# CMOY_Pro_1_0.net
KiCad netlist of a schematic drawn in Altium Designer
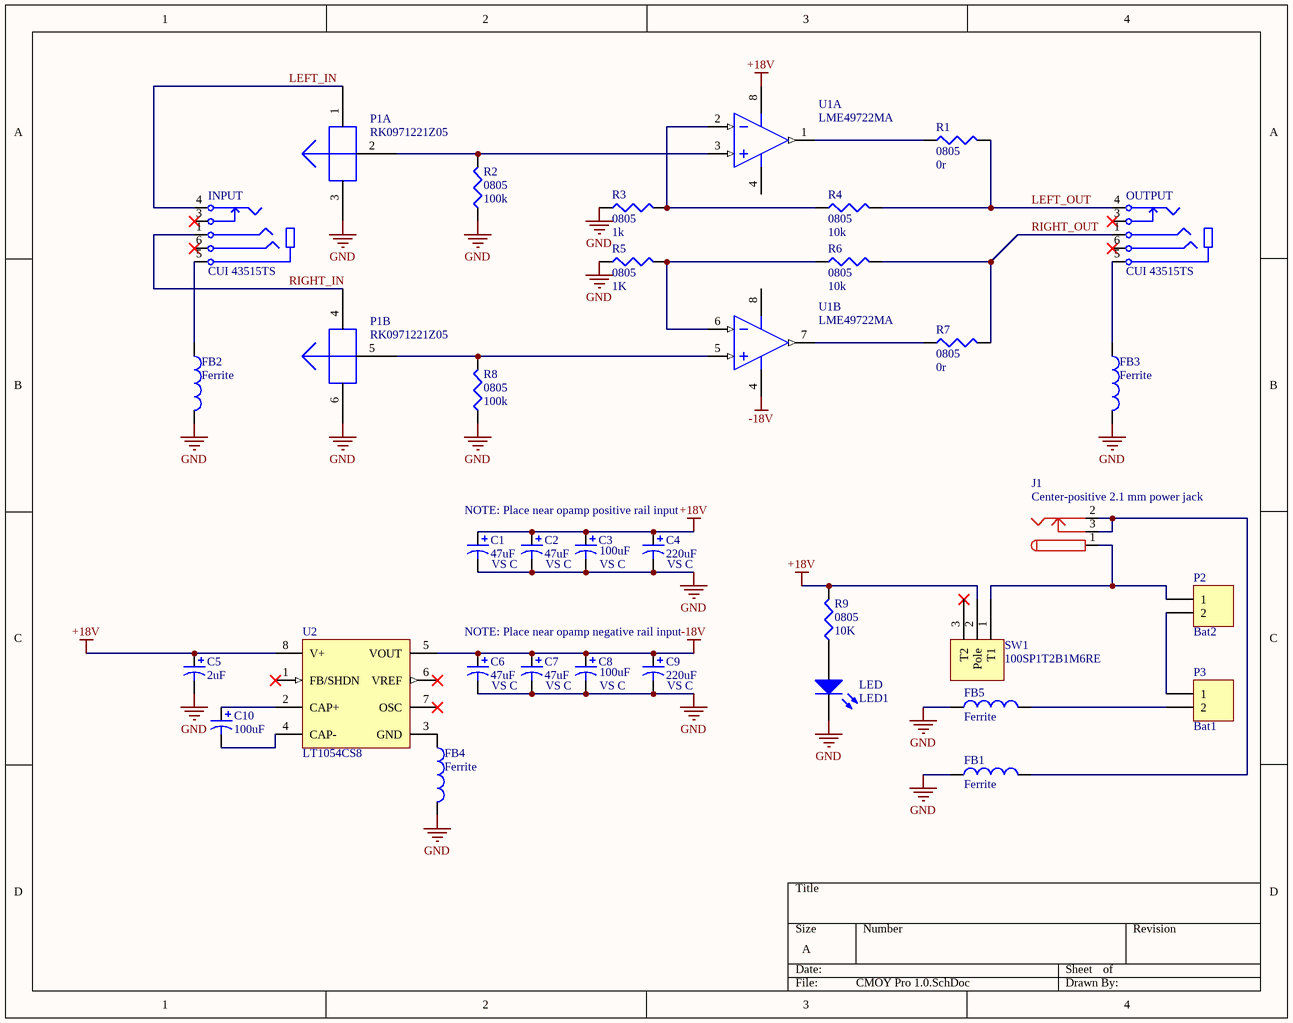
[diagram p0: CMOY Pro 1.0.SchDoc]

(export (version "E")
  (design (tool "Eeschema 10.0.6"))
  (components
    (comp (ref "C1")
      (value "VS C")
      (footprint "CAPPR2.5-6.3x5")
      (description "Polarized Capacitor (Radial)")
      (fields (field (name "ALTIUM_VALUE") "47uF") (field (name "PUBLISHER") "Altium Limited"))
      (libsource (lib "Miscellaneous Devices") (part "Cap Pol1"))
    )
    (comp (ref "C2")
      (value "VS C")
      (footprint "CAPPR2.5-6.3x5")
      (description "Polarized Capacitor (Radial)")
      (fields (field (name "ALTIUM_VALUE") "47uF") (field (name "PUBLISHER") "Altium Limited"))
      (libsource (lib "Miscellaneous Devices") (part "Cap Pol1"))
    )
    (comp (ref "C3")
      (value "VS C")
      (footprint "CAPPR2.5-6.3x5")
      (description "Polarized Capacitor (Radial)")
      (fields (field (name "ALTIUM_VALUE") "100uF") (field (name "PUBLISHER") "Altium Limited"))
      (libsource (lib "Miscellaneous Devices") (part "Cap Pol1"))
    )
    (comp (ref "C4")
      (value "VS C")
      (footprint "CAPPR2.5-6.3x5")
      (description "Polarized Capacitor (Radial)")
      (fields (field (name "ALTIUM_VALUE") "220uF") (field (name "PUBLISHER") "Altium Limited"))
      (libsource (lib "Miscellaneous Devices") (part "Cap Pol1"))
    )
    (comp (ref "C5")
      (value "2uF")
      (footprint "Panasonic VS C")
      (description "Polarized Capacitor (Radial)")
      (fields (field (name "Comment") "Cap Pol1") (field (name "PUBLISHER") "Altium Limited"))
      (libsource (lib "Miscellaneous Devices") (part "Cap Pol1"))
    )
    (comp (ref "C6")
      (value "VS C")
      (footprint "CAPPR2.5-6.3x5")
      (description "Polarized Capacitor (Radial)")
      (fields (field (name "ALTIUM_VALUE") "47uF") (field (name "PUBLISHER") "Altium Limited"))
      (libsource (lib "Miscellaneous Devices") (part "Cap Pol1"))
    )
    (comp (ref "C7")
      (value "VS C")
      (footprint "CAPPR2.5-6.3x5")
      (description "Polarized Capacitor (Radial)")
      (fields (field (name "ALTIUM_VALUE") "47uF") (field (name "PUBLISHER") "Altium Limited"))
      (libsource (lib "Miscellaneous Devices") (part "Cap Pol1"))
    )
    (comp (ref "C8")
      (value "VS C")
      (footprint "CAPPR2.5-6.3x5")
      (description "Polarized Capacitor (Radial)")
      (fields (field (name "ALTIUM_VALUE") "100uF") (field (name "PUBLISHER") "Altium Limited"))
      (libsource (lib "Miscellaneous Devices") (part "Cap Pol1"))
    )
    (comp (ref "C9")
      (value "VS C")
      (footprint "CAPPR2.5-6.3x5")
      (description "Polarized Capacitor (Radial)")
      (fields (field (name "ALTIUM_VALUE") "220uF") (field (name "PUBLISHER") "Altium Limited"))
      (libsource (lib "Miscellaneous Devices") (part "Cap Pol1"))
    )
    (comp (ref "C10")
      (value "100uF")
      (footprint "Panasonic VS C")
      (description "Polarized Capacitor (Radial)")
      (fields (field (name "Comment") "Cap Pol1") (field (name "PUBLISHER") "Altium Limited"))
      (libsource (lib "Miscellaneous Devices") (part "Cap Pol1"))
    )
    (comp (ref "FB1")
      (value "Ferrite")
      (footprint "SM 0805 - gap trimmed")
      (description "Inductor")
      (fields (field (name "PUBLISHER") "Altium Limited"))
      (libsource (lib "Miscellaneous Devices") (part "Inductor"))
    )
    (comp (ref "FB2")
      (value "Ferrite")
      (footprint "SM 0805 - gap trimmed")
      (description "Inductor")
      (fields (field (name "PUBLISHER") "Altium Limited"))
      (libsource (lib "Miscellaneous Devices") (part "Inductor"))
    )
    (comp (ref "FB3")
      (value "Ferrite")
      (footprint "SM 0805 - gap trimmed")
      (description "Inductor")
      (fields (field (name "PUBLISHER") "Altium Limited"))
      (libsource (lib "Miscellaneous Devices") (part "Inductor"))
    )
    (comp (ref "FB4")
      (value "Ferrite")
      (footprint "SM 0805 - gap trimmed")
      (description "Inductor")
      (fields (field (name "PUBLISHER") "Altium Limited"))
      (libsource (lib "Miscellaneous Devices") (part "Inductor"))
    )
    (comp (ref "FB5")
      (value "Ferrite")
      (footprint "SM 0805 - gap trimmed")
      (description "Inductor")
      (fields (field (name "PUBLISHER") "Altium Limited"))
      (libsource (lib "Miscellaneous Devices") (part "Inductor"))
    )
    (comp (ref "INPUT")
      (value "CUI 43515TS")
      (footprint "CUI SJ-43515TS")
      (libsource (lib "Adams Altium Library") (part "CUI 43515TS"))
    )
    (comp (ref "J1")
      (value "Center-positive 2.1 mm power jack")
      (footprint "PJ-102AH")
      (description "Power jack")
      (fields (field (name "PUBLISHER") "Altium Limited"))
      (libsource (lib "Adams Altium Library") (part "PWR2.5"))
    )
    (comp (ref "LED")
      (value "LED1")
      (footprint "SM 0805 polarized")
      (description "Typical RED GaAs LED")
      (fields (field (name "PUBLISHER") "Altium Limited"))
      (libsource (lib "Miscellaneous Devices") (part "LED1"))
    )
    (comp (ref "OUTPUT")
      (value "CUI 43515TS")
      (footprint "CUI SJ-43515TS")
      (libsource (lib "Adams Altium Library") (part "CUI 43515TS"))
    )
    (comp (ref "P1")
      (value "RK0971221Z05")
      (footprint "RK0971221Z05")
      (description "PCB Mount Dual Ganged 10K Pot")
      (libsource (lib "CMOY Pro Lib") (part "RK0971221Z05"))
    )
    (comp (ref "P2")
      (value "Bat2")
      (footprint "HDR1X2")
      (description "Header, 2-Pin")
      (fields (field (name "PUBLISHER") "Altium Limited"))
      (libsource (lib "Miscellaneous Connectors") (part "Header 2"))
    )
    (comp (ref "P3")
      (value "Bat1")
      (footprint "HDR1X2")
      (description "Header, 2-Pin")
      (fields (field (name "PUBLISHER") "Altium Limited"))
      (libsource (lib "Miscellaneous Connectors") (part "Header 2"))
    )
    (comp (ref "R1")
      (value "0805")
      (footprint "SM 0805 - gap trimmed")
      (description "Resistor")
      (fields (field (name "ALTIUM_VALUE") "0r") (field (name "PUBLISHER") "Altium Limited"))
      (libsource (lib "Miscellaneous Devices") (part "Res3"))
    )
    (comp (ref "R2")
      (value "0805")
      (footprint "SM 0805 - gap trimmed")
      (description "Resistor")
      (fields (field (name "ALTIUM_VALUE") "100k") (field (name "PUBLISHER") "Altium Limited"))
      (libsource (lib "Miscellaneous Devices") (part "Res3"))
    )
    (comp (ref "R3")
      (value "0805")
      (footprint "SM 0805 - gap trimmed")
      (description "Resistor")
      (fields (field (name "ALTIUM_VALUE") "1k") (field (name "PUBLISHER") "Altium Limited"))
      (libsource (lib "Miscellaneous Devices") (part "Res3"))
    )
    (comp (ref "R4")
      (value "0805")
      (footprint "SM 0805 - gap trimmed")
      (description "Resistor")
      (fields (field (name "ALTIUM_VALUE") "10k") (field (name "PUBLISHER") "Altium Limited"))
      (libsource (lib "Miscellaneous Devices") (part "Res3"))
    )
    (comp (ref "R5")
      (value "0805")
      (footprint "SM 0805 - gap trimmed")
      (description "Resistor")
      (fields (field (name "ALTIUM_VALUE") "1K") (field (name "PUBLISHER") "Altium Limited"))
      (libsource (lib "Miscellaneous Devices") (part "Res3"))
    )
    (comp (ref "R6")
      (value "0805")
      (footprint "SM 0805 - gap trimmed")
      (description "Resistor")
      (fields (field (name "ALTIUM_VALUE") "10k") (field (name "PUBLISHER") "Altium Limited"))
      (libsource (lib "Miscellaneous Devices") (part "Res3"))
    )
    (comp (ref "R7")
      (value "0805")
      (footprint "SM 0805 - gap trimmed")
      (description "Resistor")
      (fields (field (name "ALTIUM_VALUE") "0r") (field (name "PUBLISHER") "Altium Limited"))
      (libsource (lib "Miscellaneous Devices") (part "Res3"))
    )
    (comp (ref "R8")
      (value "0805")
      (footprint "SM 0805 - gap trimmed")
      (description "Resistor")
      (fields (field (name "ALTIUM_VALUE") "100k") (field (name "PUBLISHER") "Altium Limited"))
      (libsource (lib "Miscellaneous Devices") (part "Res3"))
    )
    (comp (ref "R9")
      (value "0805")
      (footprint "SM 0805 - gap trimmed")
      (description "Resistor")
      (fields (field (name "ALTIUM_VALUE") "10K") (field (name "PUBLISHER") "Altium Limited"))
      (libsource (lib "Miscellaneous Devices") (part "Res3"))
    )
    (comp (ref "SW1")
      (value "100SP1T2B1M6RE")
      (footprint "100SP1T2B1M6RE")
      (description "Right angle PCB Mount Toggle Switch")
      (libsource (lib "CMOY Pro Lib") (part "100SP1T2B1M6RE"))
    )
    (comp (ref "U1")
      (value "LME49722MA")
      (footprint "M08A_N")
      (description "Low Noise, High Performance, High Fidelity Dual Audio Operational Amplifier, 8-pin Narrow SOIC")
      (fields (field (name "MANUFACTURER") "National Semiconductor"))
      (libsource (lib "National Semiconductor Audio") (part "LME49722MA"))
    )
    (comp (ref "U2")
      (value "LT1054CS8")
      (footprint "LT-S8-8_N")
      (fields (field (name "MANUFACTURER") "Linear Technology"))
      (libsource (lib "Linear Technology Power Management Inductorless (Charge Pump) DC-DC Converters") (part "LT1054CS8"))
    )
  )
  (nets
    (net (code "1") (name "+18V") (class "Default")
      (node (ref "C1") (pin "1") (pinfunction "1_1") (pintype "passive"))
      (node (ref "C2") (pin "1") (pinfunction "1_1") (pintype "passive"))
      (node (ref "C3") (pin "1") (pinfunction "1_1") (pintype "passive"))
      (node (ref "C4") (pin "1") (pinfunction "1_1") (pintype "passive"))
      (node (ref "C5") (pin "1") (pinfunction "1_1") (pintype "passive"))
      (node (ref "R9") (pin "2") (pinfunction "2_2") (pintype "passive"))
      (node (ref "SW1") (pin "2") (pinfunction "Pole_2") (pintype "passive"))
      (node (ref "U1") (pin "8") (pinfunction "V+_8") (pintype "power_in"))
      (node (ref "U2") (pin "8") (pinfunction "V+_8") (pintype "power_in"))
    )
    (net (code "2") (name "-18V") (class "Default")
      (node (ref "C6") (pin "1") (pinfunction "1_1") (pintype "passive"))
      (node (ref "C7") (pin "1") (pinfunction "1_1") (pintype "passive"))
      (node (ref "C8") (pin "1") (pinfunction "1_1") (pintype "passive"))
      (node (ref "C9") (pin "1") (pinfunction "1_1") (pintype "passive"))
      (node (ref "U1") (pin "4") (pinfunction "V-_4") (pintype "power_in"))
      (node (ref "U2") (pin "5") (pinfunction "VOUT_5") (pintype "power_in"))
    )
    (net (code "3") (name "/LEFT_IN") (class "Default")
      (node (ref "INPUT") (pin "4") (pinfunction "TIP_4") (pintype "passive"))
      (node (ref "P1") (pin "1") (pinfunction "1_1") (pintype "passive"))
    )
    (net (code "4") (name "/LEFT_OUT") (class "Default")
      (node (ref "OUTPUT") (pin "4") (pinfunction "TIP_4") (pintype "passive"))
      (node (ref "R1") (pin "2") (pinfunction "2_2") (pintype "passive"))
      (node (ref "R4") (pin "2") (pinfunction "2_2") (pintype "passive"))
    )
    (net (code "5") (name "/RIGHT_IN") (class "Default")
      (node (ref "INPUT") (pin "1") (pinfunction "R1_1") (pintype "passive"))
      (node (ref "P1") (pin "4") (pinfunction "4_4") (pintype "passive"))
    )
    (net (code "6") (name "/RIGHT_OUT") (class "Default")
      (node (ref "OUTPUT") (pin "1") (pinfunction "R1_1") (pintype "passive"))
      (node (ref "R6") (pin "2") (pinfunction "2_2") (pintype "passive"))
      (node (ref "R7") (pin "2") (pinfunction "2_2") (pintype "passive"))
    )
    (net (code "7") (name "GND") (class "Default")
      (node (ref "C1") (pin "2") (pinfunction "2_2") (pintype "passive"))
      (node (ref "C2") (pin "2") (pinfunction "2_2") (pintype "passive"))
      (node (ref "C3") (pin "2") (pinfunction "2_2") (pintype "passive"))
      (node (ref "C4") (pin "2") (pinfunction "2_2") (pintype "passive"))
      (node (ref "C5") (pin "2") (pinfunction "2_2") (pintype "passive"))
      (node (ref "C6") (pin "2") (pinfunction "2_2") (pintype "passive"))
      (node (ref "C7") (pin "2") (pinfunction "2_2") (pintype "passive"))
      (node (ref "C8") (pin "2") (pinfunction "2_2") (pintype "passive"))
      (node (ref "C9") (pin "2") (pinfunction "2_2") (pintype "passive"))
      (node (ref "FB1") (pin "1") (pinfunction "1_1") (pintype "passive"))
      (node (ref "FB2") (pin "2") (pinfunction "2_2") (pintype "passive"))
      (node (ref "FB3") (pin "2") (pinfunction "2_2") (pintype "passive"))
      (node (ref "FB4") (pin "2") (pinfunction "2_2") (pintype "passive"))
      (node (ref "FB5") (pin "1") (pinfunction "1_1") (pintype "passive"))
      (node (ref "LED") (pin "1") (pinfunction "A_1") (pintype "passive"))
      (node (ref "P1") (pin "3") (pinfunction "3_3") (pintype "passive"))
      (node (ref "P1") (pin "6") (pinfunction "6_6") (pintype "passive"))
      (node (ref "R2") (pin "1") (pinfunction "1_1") (pintype "passive"))
      (node (ref "R3") (pin "1") (pinfunction "1_1") (pintype "passive"))
      (node (ref "R5") (pin "1") (pinfunction "1_1") (pintype "passive"))
      (node (ref "R8") (pin "1") (pinfunction "1_1") (pintype "passive"))
    )
    (net (code "8") (name "Net-(FB1-Pad2)") (class "Default")
      (node (ref "FB1") (pin "2") (pinfunction "2_2") (pintype "passive"))
      (node (ref "J1") (pin "2") (pinfunction "2_2") (pintype "power_in"))
      (node (ref "J1") (pin "3") (pinfunction "3_3") (pintype "power_in"))
    )
    (net (code "9") (name "Net-(FB5-Pad2)") (class "Default")
      (node (ref "FB5") (pin "2") (pinfunction "2_2") (pintype "passive"))
      (node (ref "P3") (pin "2") (pinfunction "2_2") (pintype "passive"))
    )
    (net (code "10") (name "Net-(INPUT-SLEEVE)") (class "Default")
      (node (ref "FB2") (pin "1") (pinfunction "1_1") (pintype "passive"))
      (node (ref "INPUT") (pin "5") (pinfunction "SLEEVE_5") (pintype "passive"))
    )
    (net (code "11") (name "Net-(LED-K)") (class "Default")
      (node (ref "LED") (pin "2") (pinfunction "K_2") (pintype "passive"))
      (node (ref "R9") (pin "1") (pinfunction "1_1") (pintype "passive"))
    )
    (net (code "12") (name "Net-(OUTPUT-SLEEVE)") (class "Default")
      (node (ref "FB3") (pin "1") (pinfunction "1_1") (pintype "passive"))
      (node (ref "OUTPUT") (pin "5") (pinfunction "SLEEVE_5") (pintype "passive"))
    )
    (net (code "13") (name "Net-(P1-Pad2)") (class "Default")
      (node (ref "P1") (pin "2") (pinfunction "2_2") (pintype "passive"))
      (node (ref "R2") (pin "2") (pinfunction "2_2") (pintype "passive"))
      (node (ref "U1") (pin "3") (pinfunction "IN_A_3") (pintype "input"))
    )
    (net (code "14") (name "Net-(P1-Pad5)") (class "Default")
      (node (ref "P1") (pin "5") (pinfunction "5_5") (pintype "passive"))
      (node (ref "R8") (pin "2") (pinfunction "2_2") (pintype "passive"))
      (node (ref "U1") (pin "5") (pinfunction "IN_B_5") (pintype "input"))
    )
    (net (code "15") (name "Net-(P2-Pad2)") (class "Default")
      (node (ref "P2") (pin "2") (pinfunction "2_2") (pintype "passive"))
      (node (ref "P3") (pin "1") (pinfunction "1_1") (pintype "passive"))
    )
    (net (code "16") (name "Net-(R3-Pad2)") (class "Default")
      (node (ref "R3") (pin "2") (pinfunction "2_2") (pintype "passive"))
      (node (ref "R4") (pin "1") (pinfunction "1_1") (pintype "passive"))
      (node (ref "U1") (pin "2") (pinfunction "IN_A_2") (pintype "input"))
    )
    (net (code "17") (name "Net-(R5-Pad2)") (class "Default")
      (node (ref "R5") (pin "2") (pinfunction "2_2") (pintype "passive"))
      (node (ref "R6") (pin "1") (pinfunction "1_1") (pintype "passive"))
      (node (ref "U1") (pin "6") (pinfunction "IN_B_6") (pintype "input"))
    )
    (net (code "18") (name "Net-(SW1-T1)") (class "Default")
      (node (ref "J1") (pin "1") (pinfunction "1_1") (pintype "power_in"))
      (node (ref "P2") (pin "1") (pinfunction "1_1") (pintype "passive"))
      (node (ref "SW1") (pin "1") (pinfunction "T1_1") (pintype "passive"))
    )
    (net (code "19") (name "Net-(U1A-OUT_A)") (class "Default")
      (node (ref "R1") (pin "1") (pinfunction "1_1") (pintype "passive"))
      (node (ref "U1") (pin "1") (pinfunction "OUT_A_1") (pintype "output"))
    )
    (net (code "20") (name "Net-(U1B-OUT_B)") (class "Default")
      (node (ref "R7") (pin "1") (pinfunction "1_1") (pintype "passive"))
      (node (ref "U1") (pin "7") (pinfunction "OUT_B_7") (pintype "output"))
    )
    (net (code "21") (name "Net-(U2-CAP+)") (class "Default")
      (node (ref "C10") (pin "1") (pinfunction "1_1") (pintype "passive"))
      (node (ref "U2") (pin "2") (pinfunction "CAP+_2") (pintype "passive"))
    )
    (net (code "22") (name "Net-(U2-CAP-)") (class "Default")
      (node (ref "C10") (pin "2") (pinfunction "2_2") (pintype "passive"))
      (node (ref "U2") (pin "4") (pinfunction "CAP-_4") (pintype "passive"))
    )
    (net (code "23") (name "Net-(U2-GND)") (class "Default")
      (node (ref "FB4") (pin "1") (pinfunction "1_1") (pintype "passive"))
      (node (ref "U2") (pin "3") (pinfunction "GND_3") (pintype "power_in"))
    )
    (net (code "24") (name "unconnected-(INPUT-R2-Pad6)") (class "Default")
      (node (ref "INPUT") (pin "6") (pinfunction "R2_6") (pintype "passive+no_connect"))
    )
    (net (code "25") (name "unconnected-(INPUT-TS-Pad3)") (class "Default")
      (node (ref "INPUT") (pin "3") (pinfunction "TS_3") (pintype "passive+no_connect"))
    )
    (net (code "26") (name "unconnected-(OUTPUT-R2-Pad6)") (class "Default")
      (node (ref "OUTPUT") (pin "6") (pinfunction "R2_6") (pintype "passive+no_connect"))
    )
    (net (code "27") (name "unconnected-(OUTPUT-TS-Pad3)") (class "Default")
      (node (ref "OUTPUT") (pin "3") (pinfunction "TS_3") (pintype "passive+no_connect"))
    )
    (net (code "28") (name "unconnected-(SW1-NC-Pad4)") (class "Default")
      (node (ref "SW1") (pin "4") (pinfunction "NC_4") (pintype "passive"))
    )
    (net (code "29") (name "unconnected-(SW1-NC-Pad5)") (class "Default")
      (node (ref "SW1") (pin "5") (pinfunction "NC_5") (pintype "passive"))
    )
    (net (code "30") (name "unconnected-(SW1-T2-Pad3)") (class "Default")
      (node (ref "SW1") (pin "3") (pinfunction "T2_3") (pintype "passive+no_connect"))
    )
    (net (code "31") (name "unconnected-(U1A-V--Pad4)") (class "Default")
      (node (ref "U1") (pin "4") (pinfunction "V-_4") (pintype "power_in"))
    )
    (net (code "32") (name "unconnected-(U1B-V+-Pad8)") (class "Default")
      (node (ref "U1") (pin "8") (pinfunction "V+_8") (pintype "power_in"))
    )
    (net (code "33") (name "unconnected-(U2-FB{slash}SHDN-Pad1)") (class "Default")
      (node (ref "U2") (pin "1") (pinfunction "FB/SHDN_1") (pintype "input+no_connect"))
    )
    (net (code "34") (name "unconnected-(U2-OSC-Pad7)") (class "Default")
      (node (ref "U2") (pin "7") (pinfunction "OSC_7") (pintype "passive+no_connect"))
    )
    (net (code "35") (name "unconnected-(U2-VREF-Pad6)") (class "Default")
      (node (ref "U2") (pin "6") (pinfunction "VREF_6") (pintype "output+no_connect"))
    )
  )
)
